# mcc_dac_amp.net
KiCad netlist of a schematic drawn in Altium Designer
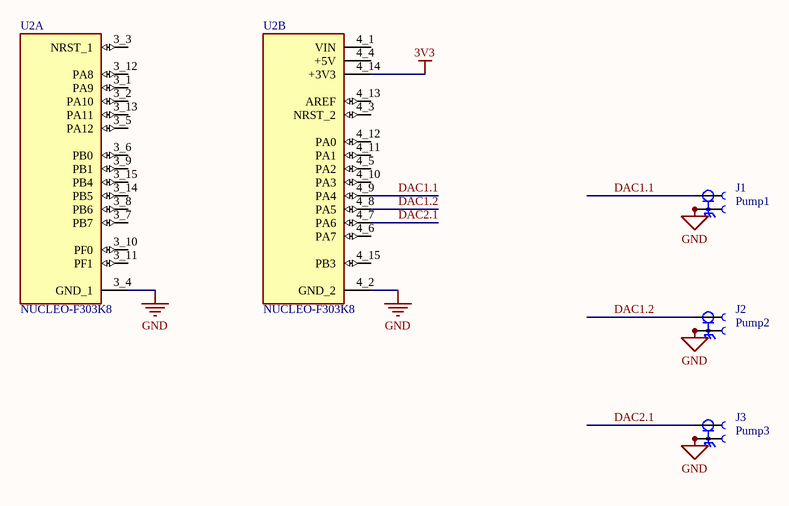
[diagram p0: mcc_dac_amp.SchDoc]

(export (version "E")
  (design (tool "Eeschema 10.0.6"))
  (components
    (comp (ref "J1")
      (value "Pump1")
      (footprint "CONBNC002:LINX_CONBNC002")
      (description "CONBNC002")
      (fields (field (name "MF") "{'manufacturer': u'TE Connectivity'}"))
      (libsource (lib "*") (part "CONBNC002"))
    )
    (comp (ref "J2")
      (value "Pump2")
      (footprint "CONBNC002:LINX_CONBNC002")
      (description "CONBNC002")
      (fields (field (name "MF") "{'manufacturer': u'TE Connectivity'}"))
      (libsource (lib "*") (part "CONBNC002"))
    )
    (comp (ref "J3")
      (value "Pump3")
      (footprint "CONBNC002:LINX_CONBNC002")
      (description "CONBNC002")
      (fields (field (name "MF") "{'manufacturer': u'TE Connectivity'}"))
      (libsource (lib "*") (part "CONBNC002"))
    )
    (comp (ref "U2")
      (value "NUCLEO-F303K8")
      (footprint "NUCLEO-F303K8:MODULE_NUCLEO-F303K8")
      (fields (field (name "MF") "{'manufacturer': u'STMicroelectronics'}"))
      (libsource (lib "NUCLEO-F303K8") (part "NUCLEO-F303K8"))
    )
  )
  (nets
    (net (code "1") (name "/DAC1.1") (class "Default")
      (node (ref "J1") (pin "1") (pinfunction "1_1") (pintype "passive"))
      (node (ref "U2") (pin "4_9") (pinfunction "PA4_4_9") (pintype "bidirectional"))
    )
    (net (code "2") (name "/DAC1.2") (class "Default")
      (node (ref "J2") (pin "1") (pinfunction "1_1") (pintype "passive"))
      (node (ref "U2") (pin "4_8") (pinfunction "PA5_4_8") (pintype "bidirectional"))
    )
    (net (code "3") (name "/DAC2.1") (class "Default")
      (node (ref "J3") (pin "1") (pinfunction "1_1") (pintype "passive"))
      (node (ref "U2") (pin "4_7") (pinfunction "PA6_4_7") (pintype "bidirectional"))
    )
    (net (code "4") (name "3V3") (class "Default")
      (node (ref "U2") (pin "4_14") (pinfunction "+3V3_4_14") (pintype "power_in"))
    )
    (net (code "5") (name "GND") (class "Default")
      (node (ref "J1") (pin "2") (pinfunction "2_2") (pintype "passive"))
      (node (ref "J1") (pin "S1") (pinfunction "2_S1") (pintype "passive"))
      (node (ref "J1") (pin "S2") (pinfunction "2_S2") (pintype "passive"))
      (node (ref "J2") (pin "2") (pinfunction "2_2") (pintype "passive"))
      (node (ref "J2") (pin "S1") (pinfunction "2_S1") (pintype "passive"))
      (node (ref "J2") (pin "S2") (pinfunction "2_S2") (pintype "passive"))
      (node (ref "J3") (pin "2") (pinfunction "2_2") (pintype "passive"))
      (node (ref "J3") (pin "S1") (pinfunction "2_S1") (pintype "passive"))
      (node (ref "J3") (pin "S2") (pinfunction "2_S2") (pintype "passive"))
      (node (ref "U2") (pin "3_4") (pinfunction "GND_1_3_4") (pintype "power_in"))
      (node (ref "U2") (pin "4_2") (pinfunction "GND_2_4_2") (pintype "power_in"))
    )
    (net (code "6") (name "unconnected-(U2A-NRST_1-Pad3_3)") (class "Default")
      (node (ref "U2") (pin "3_3") (pinfunction "NRST_1_3_3") (pintype "bidirectional"))
    )
    (net (code "7") (name "unconnected-(U2A-PA8-Pad3_12)") (class "Default")
      (node (ref "U2") (pin "3_12") (pinfunction "PA8_3_12") (pintype "bidirectional"))
    )
    (net (code "8") (name "unconnected-(U2A-PA9-Pad3_1)") (class "Default")
      (node (ref "U2") (pin "3_1") (pinfunction "PA9_3_1") (pintype "bidirectional"))
    )
    (net (code "9") (name "unconnected-(U2A-PA10-Pad3_2)") (class "Default")
      (node (ref "U2") (pin "3_2") (pinfunction "PA10_3_2") (pintype "bidirectional"))
    )
    (net (code "10") (name "unconnected-(U2A-PA11-Pad3_13)") (class "Default")
      (node (ref "U2") (pin "3_13") (pinfunction "PA11_3_13") (pintype "bidirectional"))
    )
    (net (code "11") (name "unconnected-(U2A-PA12-Pad3_5)") (class "Default")
      (node (ref "U2") (pin "3_5") (pinfunction "PA12_3_5") (pintype "bidirectional"))
    )
    (net (code "12") (name "unconnected-(U2A-PB0-Pad3_6)") (class "Default")
      (node (ref "U2") (pin "3_6") (pinfunction "PB0_3_6") (pintype "bidirectional"))
    )
    (net (code "13") (name "unconnected-(U2A-PB1-Pad3_9)") (class "Default")
      (node (ref "U2") (pin "3_9") (pinfunction "PB1_3_9") (pintype "bidirectional"))
    )
    (net (code "14") (name "unconnected-(U2A-PB4-Pad3_15)") (class "Default")
      (node (ref "U2") (pin "3_15") (pinfunction "PB4_3_15") (pintype "bidirectional"))
    )
    (net (code "15") (name "unconnected-(U2A-PB5-Pad3_14)") (class "Default")
      (node (ref "U2") (pin "3_14") (pinfunction "PB5_3_14") (pintype "bidirectional"))
    )
    (net (code "16") (name "unconnected-(U2A-PB6-Pad3_8)") (class "Default")
      (node (ref "U2") (pin "3_8") (pinfunction "PB6_3_8") (pintype "bidirectional"))
    )
    (net (code "17") (name "unconnected-(U2A-PB7-Pad3_7)") (class "Default")
      (node (ref "U2") (pin "3_7") (pinfunction "PB7_3_7") (pintype "bidirectional"))
    )
    (net (code "18") (name "unconnected-(U2A-PF0-Pad3_10)") (class "Default")
      (node (ref "U2") (pin "3_10") (pinfunction "PF0_3_10") (pintype "bidirectional"))
    )
    (net (code "19") (name "unconnected-(U2A-PF1-Pad3_11)") (class "Default")
      (node (ref "U2") (pin "3_11") (pinfunction "PF1_3_11") (pintype "bidirectional"))
    )
    (net (code "20") (name "unconnected-(U2B-+5V-Pad4_4)") (class "Default")
      (node (ref "U2") (pin "4_4") (pinfunction "+5V_4_4") (pintype "power_in"))
    )
    (net (code "21") (name "unconnected-(U2B-AREF-Pad4_13)") (class "Default")
      (node (ref "U2") (pin "4_13") (pinfunction "AREF_4_13") (pintype "bidirectional"))
    )
    (net (code "22") (name "unconnected-(U2B-NRST_2-Pad4_3)") (class "Default")
      (node (ref "U2") (pin "4_3") (pinfunction "NRST_2_4_3") (pintype "bidirectional"))
    )
    (net (code "23") (name "unconnected-(U2B-PA0-Pad4_12)") (class "Default")
      (node (ref "U2") (pin "4_12") (pinfunction "PA0_4_12") (pintype "bidirectional"))
    )
    (net (code "24") (name "unconnected-(U2B-PA1-Pad4_11)") (class "Default")
      (node (ref "U2") (pin "4_11") (pinfunction "PA1_4_11") (pintype "bidirectional"))
    )
    (net (code "25") (name "unconnected-(U2B-PA2-Pad4_5)") (class "Default")
      (node (ref "U2") (pin "4_5") (pinfunction "PA2_4_5") (pintype "bidirectional"))
    )
    (net (code "26") (name "unconnected-(U2B-PA3-Pad4_10)") (class "Default")
      (node (ref "U2") (pin "4_10") (pinfunction "PA3_4_10") (pintype "bidirectional"))
    )
    (net (code "27") (name "unconnected-(U2B-PA7-Pad4_6)") (class "Default")
      (node (ref "U2") (pin "4_6") (pinfunction "PA7_4_6") (pintype "bidirectional"))
    )
    (net (code "28") (name "unconnected-(U2B-PB3-Pad4_15)") (class "Default")
      (node (ref "U2") (pin "4_15") (pinfunction "PB3_4_15") (pintype "bidirectional"))
    )
    (net (code "29") (name "unconnected-(U2B-VIN-Pad4_1)") (class "Default")
      (node (ref "U2") (pin "4_1") (pinfunction "VIN_4_1") (pintype "power_in"))
    )
  )
)
